# TPS7A47_module_A.net
KiCad netlist of a schematic drawn in EAGLE
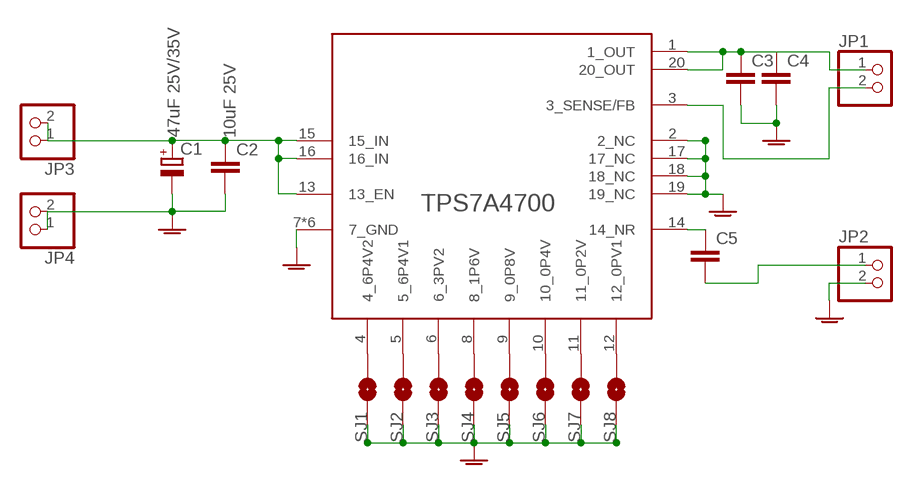
[diagram p0: schematic, sheet 1]

(export (version "E")
  (design (tool "Eeschema 10.0.6"))
  (components
    (comp (ref "C1")
      (value "47uF 25V/35V")
      (footprint "eagle-import:D_7343-31R")
      (libsource (lib "eagle-import") (part "CPOL-EUD/7343-31R"))
    )
    (comp (ref "C2")
      (value "10uF 25V")
      (footprint "eagle-import:C0805K")
      (libsource (lib "eagle-import") (part "C-EUC0805K"))
    )
    (comp (ref "C3")
      (value "C-EUC1206")
      (footprint "eagle-import:C1206")
      (libsource (lib "eagle-import") (part "C-EUC1206"))
    )
    (comp (ref "C4")
      (value "C-EUC1206")
      (footprint "eagle-import:C1206")
      (libsource (lib "eagle-import") (part "C-EUC1206"))
    )
    (comp (ref "C5")
      (value "C-EUC0805")
      (footprint "eagle-import:C0805")
      (libsource (lib "eagle-import") (part "C-EUC0805"))
    )
    (comp (ref "IC")
      (value "TPS7A4701")
      (footprint "eagle-import:VQFN20")
      (libsource (lib "eagle-import") (part "TPS7A4701"))
    )
    (comp (ref "JP1")
      (value "PINHD-1X2")
      (footprint "eagle-import:1X02")
      (libsource (lib "eagle-import") (part "PINHD-1X2"))
    )
    (comp (ref "JP2")
      (value "PINHD-1X2")
      (footprint "eagle-import:1X02")
      (libsource (lib "eagle-import") (part "PINHD-1X2"))
    )
    (comp (ref "JP3")
      (value "PINHD-1X2")
      (footprint "eagle-import:1X02")
      (libsource (lib "eagle-import") (part "PINHD-1X2"))
    )
    (comp (ref "JP4")
      (value "PINHD-1X2")
      (footprint "eagle-import:1X02")
      (libsource (lib "eagle-import") (part "PINHD-1X2"))
    )
    (comp (ref "SJ1")
      (value "SOLDERJUMPERNO")
      (footprint "eagle-import:SJ_2S-NO")
      (libsource (lib "eagle-import") (part "SOLDERJUMPERNO"))
    )
    (comp (ref "SJ2")
      (value "SOLDERJUMPERNO")
      (footprint "eagle-import:SJ_2S-NO")
      (libsource (lib "eagle-import") (part "SOLDERJUMPERNO"))
    )
    (comp (ref "SJ3")
      (value "SOLDERJUMPERNO")
      (footprint "eagle-import:SJ_2S-NO")
      (libsource (lib "eagle-import") (part "SOLDERJUMPERNO"))
    )
    (comp (ref "SJ4")
      (value "SOLDERJUMPERNO")
      (footprint "eagle-import:SJ_2S-NO")
      (libsource (lib "eagle-import") (part "SOLDERJUMPERNO"))
    )
    (comp (ref "SJ5")
      (value "SOLDERJUMPERNO")
      (footprint "eagle-import:SJ_2S-NO")
      (libsource (lib "eagle-import") (part "SOLDERJUMPERNO"))
    )
    (comp (ref "SJ6")
      (value "SOLDERJUMPERNO")
      (footprint "eagle-import:SJ_2S-NO")
      (libsource (lib "eagle-import") (part "SOLDERJUMPERNO"))
    )
    (comp (ref "SJ7")
      (value "SOLDERJUMPERNO")
      (footprint "eagle-import:SJ_2S-NO")
      (libsource (lib "eagle-import") (part "SOLDERJUMPERNO"))
    )
    (comp (ref "SJ8")
      (value "SOLDERJUMPERNO")
      (footprint "eagle-import:SJ_2S-NO")
      (libsource (lib "eagle-import") (part "SOLDERJUMPERNO"))
    )
  )
  (nets
    (net (code "1") (name "GND") (class "Default")
      (node (ref "C1") (pin "-") (pinfunction "-_-") (pintype "passive"))
      (node (ref "C2") (pin "2") (pinfunction "2_2") (pintype "passive"))
      (node (ref "C3") (pin "2") (pinfunction "2_2") (pintype "passive"))
      (node (ref "C4") (pin "2") (pinfunction "2_2") (pintype "passive"))
      (node (ref "IC") (pin "17") (pinfunction "17_NC_17") (pintype "bidirectional"))
      (node (ref "IC") (pin "18") (pinfunction "18_NC_18") (pintype "bidirectional"))
      (node (ref "IC") (pin "19") (pinfunction "19_NC_19") (pintype "bidirectional"))
      (node (ref "IC") (pin "2") (pinfunction "2_NC_2") (pintype "bidirectional"))
      (node (ref "IC") (pin "21") (pinfunction "7_GND_21") (pintype "bidirectional"))
      (node (ref "IC") (pin "7") (pinfunction "7_GND_7") (pintype "bidirectional"))
      (node (ref "IC") (pin "P$1") (pinfunction "7_GND_P$1") (pintype "bidirectional"))
      (node (ref "IC") (pin "P$2") (pinfunction "7_GND_P$2") (pintype "bidirectional"))
      (node (ref "IC") (pin "P$3") (pinfunction "7_GND_P$3") (pintype "bidirectional"))
      (node (ref "IC") (pin "P$4") (pinfunction "7_GND_P$4") (pintype "bidirectional"))
      (node (ref "JP2") (pin "2") (pinfunction "2_2") (pintype "passive"))
      (node (ref "JP4") (pin "1") (pinfunction "1_1") (pintype "passive"))
      (node (ref "JP4") (pin "2") (pinfunction "2_2") (pintype "passive"))
      (node (ref "SJ1") (pin "1") (pinfunction "1_1") (pintype "passive"))
      (node (ref "SJ2") (pin "1") (pinfunction "1_1") (pintype "passive"))
      (node (ref "SJ3") (pin "1") (pinfunction "1_1") (pintype "passive"))
      (node (ref "SJ4") (pin "1") (pinfunction "1_1") (pintype "passive"))
      (node (ref "SJ5") (pin "1") (pinfunction "1_1") (pintype "passive"))
      (node (ref "SJ6") (pin "1") (pinfunction "1_1") (pintype "passive"))
      (node (ref "SJ7") (pin "1") (pinfunction "1_1") (pintype "passive"))
      (node (ref "SJ8") (pin "1") (pinfunction "1_1") (pintype "passive"))
    )
    (net (code "2") (name "Net-(C5-Pad2)") (class "Default")
      (node (ref "C5") (pin "2") (pinfunction "2_2") (pintype "passive"))
      (node (ref "JP2") (pin "1") (pinfunction "1_1") (pintype "passive"))
    )
    (net (code "3") (name "Net-(IC-1_OUT)") (class "Default")
      (node (ref "C3") (pin "1") (pinfunction "1_1") (pintype "passive"))
      (node (ref "C4") (pin "1") (pinfunction "1_1") (pintype "passive"))
      (node (ref "IC") (pin "1") (pinfunction "1_OUT_1") (pintype "bidirectional"))
      (node (ref "IC") (pin "20") (pinfunction "20_OUT_20") (pintype "bidirectional"))
      (node (ref "JP1") (pin "1") (pinfunction "1_1") (pintype "passive"))
    )
    (net (code "4") (name "Net-(IC-3_SENSE{slash}FB)") (class "Default")
      (node (ref "IC") (pin "3") (pinfunction "3_SENSE/FB_3") (pintype "bidirectional"))
      (node (ref "JP1") (pin "2") (pinfunction "2_2") (pintype "passive"))
    )
    (net (code "5") (name "Net-(IC-4_6P4V2)") (class "Default")
      (node (ref "IC") (pin "4") (pinfunction "4_6P4V2_4") (pintype "bidirectional"))
      (node (ref "SJ1") (pin "2") (pinfunction "2_2") (pintype "passive"))
    )
    (net (code "6") (name "Net-(IC-5_6P4V1)") (class "Default")
      (node (ref "IC") (pin "5") (pinfunction "5_6P4V1_5") (pintype "bidirectional"))
      (node (ref "SJ2") (pin "2") (pinfunction "2_2") (pintype "passive"))
    )
    (net (code "7") (name "Net-(IC-6_3PV2)") (class "Default")
      (node (ref "IC") (pin "6") (pinfunction "6_3PV2_6") (pintype "bidirectional"))
      (node (ref "SJ3") (pin "2") (pinfunction "2_2") (pintype "passive"))
    )
    (net (code "8") (name "Net-(IC-8_1P6V)") (class "Default")
      (node (ref "IC") (pin "8") (pinfunction "8_1P6V_8") (pintype "bidirectional"))
      (node (ref "SJ4") (pin "2") (pinfunction "2_2") (pintype "passive"))
    )
    (net (code "9") (name "Net-(IC-9_0P8V)") (class "Default")
      (node (ref "IC") (pin "9") (pinfunction "9_0P8V_9") (pintype "bidirectional"))
      (node (ref "SJ5") (pin "2") (pinfunction "2_2") (pintype "passive"))
    )
    (net (code "10") (name "Net-(IC-10_0P4V)") (class "Default")
      (node (ref "IC") (pin "10") (pinfunction "10_0P4V_10") (pintype "bidirectional"))
      (node (ref "SJ6") (pin "2") (pinfunction "2_2") (pintype "passive"))
    )
    (net (code "11") (name "Net-(IC-11_0P2V)") (class "Default")
      (node (ref "IC") (pin "11") (pinfunction "11_0P2V_11") (pintype "bidirectional"))
      (node (ref "SJ7") (pin "2") (pinfunction "2_2") (pintype "passive"))
    )
    (net (code "12") (name "Net-(IC-12_0PV1)") (class "Default")
      (node (ref "IC") (pin "12") (pinfunction "12_0PV1_12") (pintype "bidirectional"))
      (node (ref "SJ8") (pin "2") (pinfunction "2_2") (pintype "passive"))
    )
    (net (code "13") (name "Net-(IC-13_EN)") (class "Default")
      (node (ref "C1") (pin "+") (pinfunction "+_+") (pintype "passive"))
      (node (ref "C2") (pin "1") (pinfunction "1_1") (pintype "passive"))
      (node (ref "IC") (pin "13") (pinfunction "13_EN_13") (pintype "bidirectional"))
      (node (ref "IC") (pin "15") (pinfunction "15_IN_15") (pintype "bidirectional"))
      (node (ref "IC") (pin "16") (pinfunction "16_IN_16") (pintype "bidirectional"))
      (node (ref "JP3") (pin "1") (pinfunction "1_1") (pintype "passive"))
      (node (ref "JP3") (pin "2") (pinfunction "2_2") (pintype "passive"))
    )
    (net (code "14") (name "Net-(IC-14_NR)") (class "Default")
      (node (ref "C5") (pin "1") (pinfunction "1_1") (pintype "passive"))
      (node (ref "IC") (pin "14") (pinfunction "14_NR_14") (pintype "bidirectional"))
    )
  )
)
